# TSOC_USBUART2_R1_1.net
KiCad netlist of a schematic drawn in EAGLE
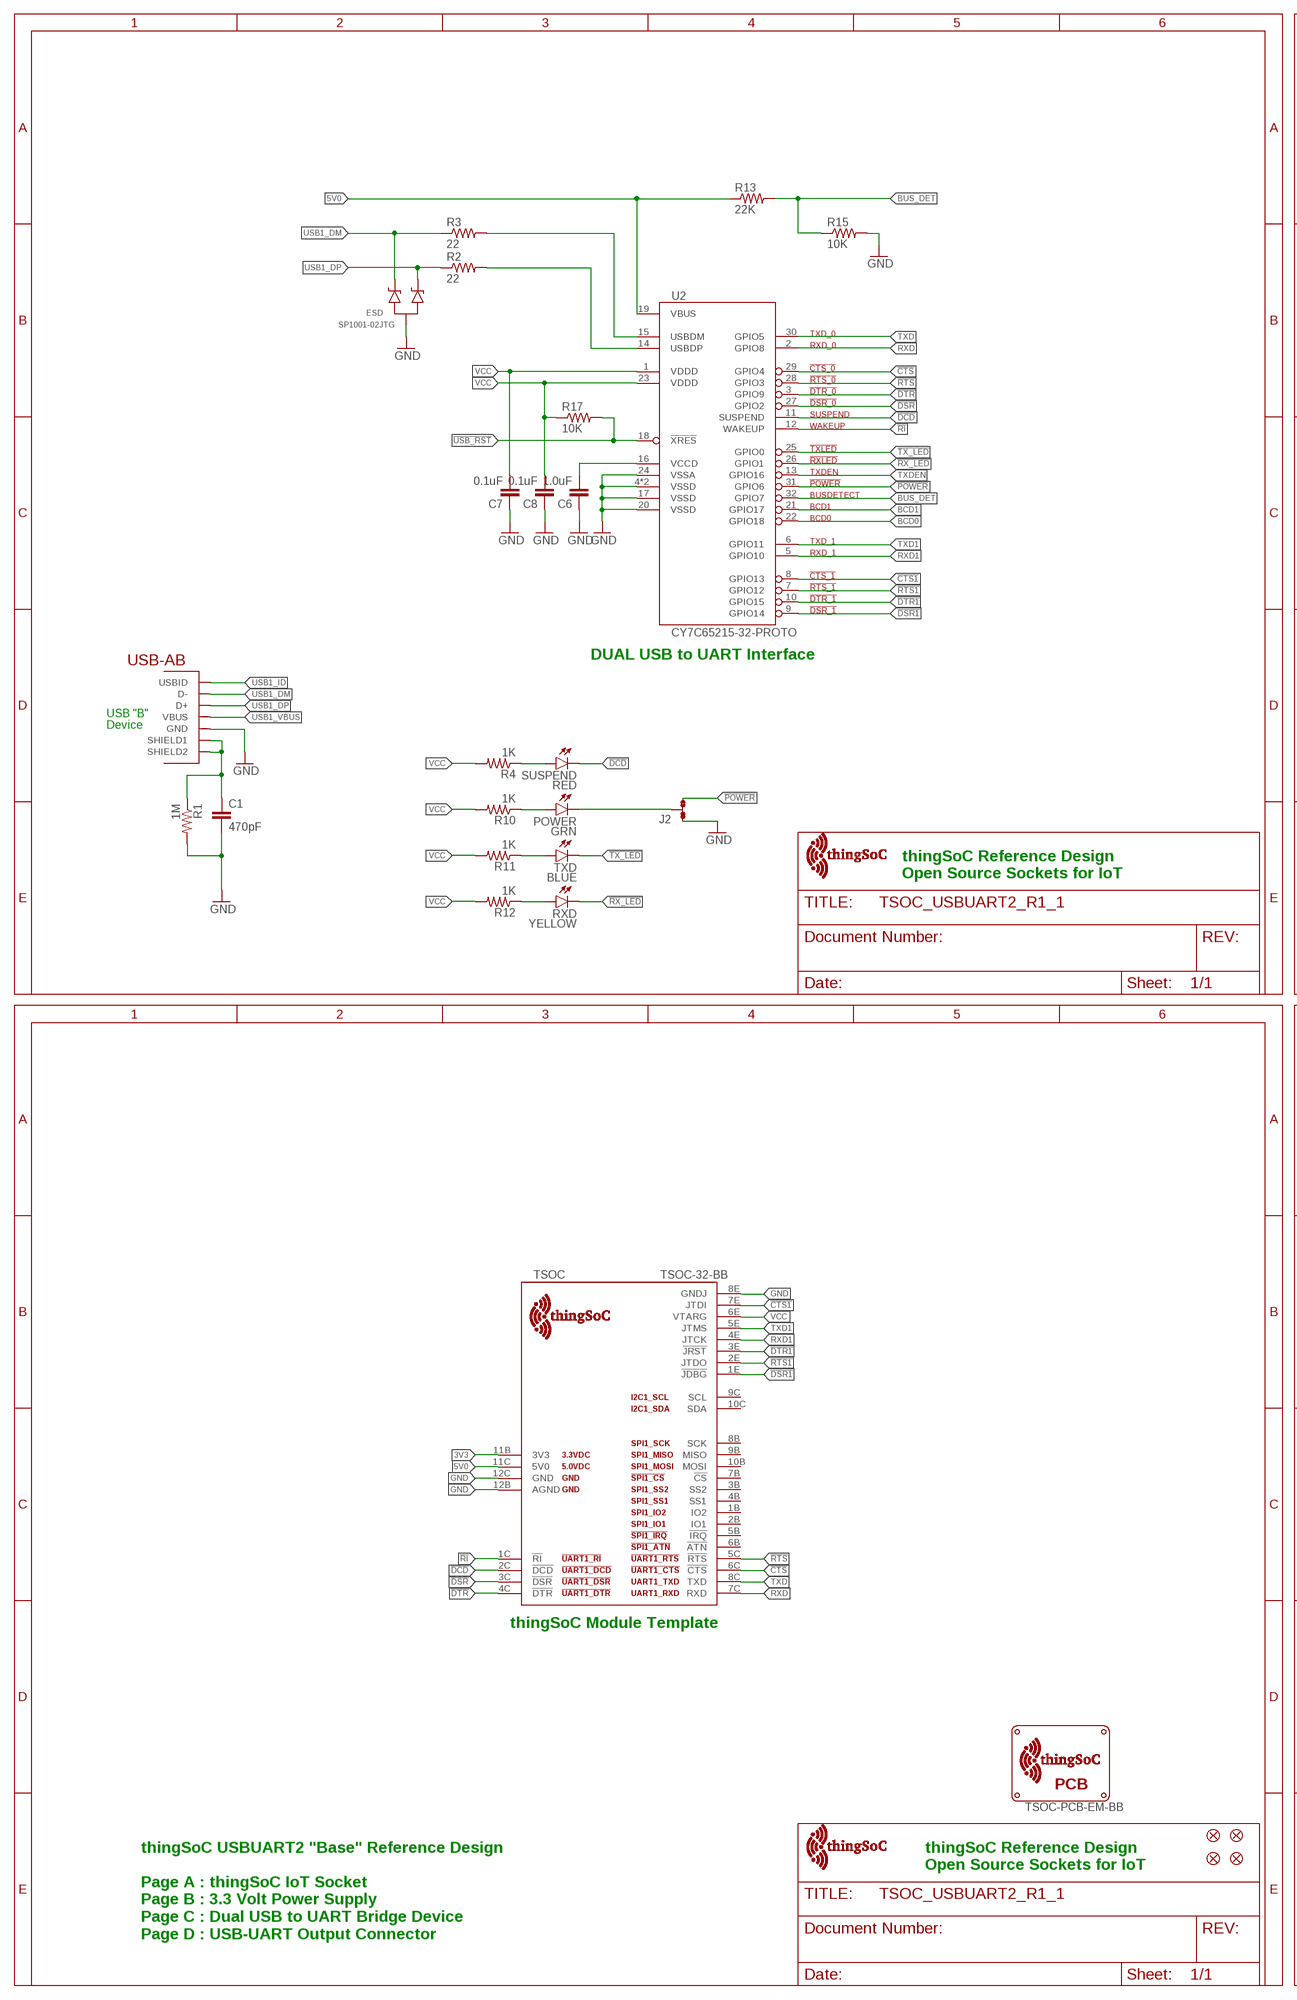
[diagram p0: schematic, sheet 1, part 1 of 2]
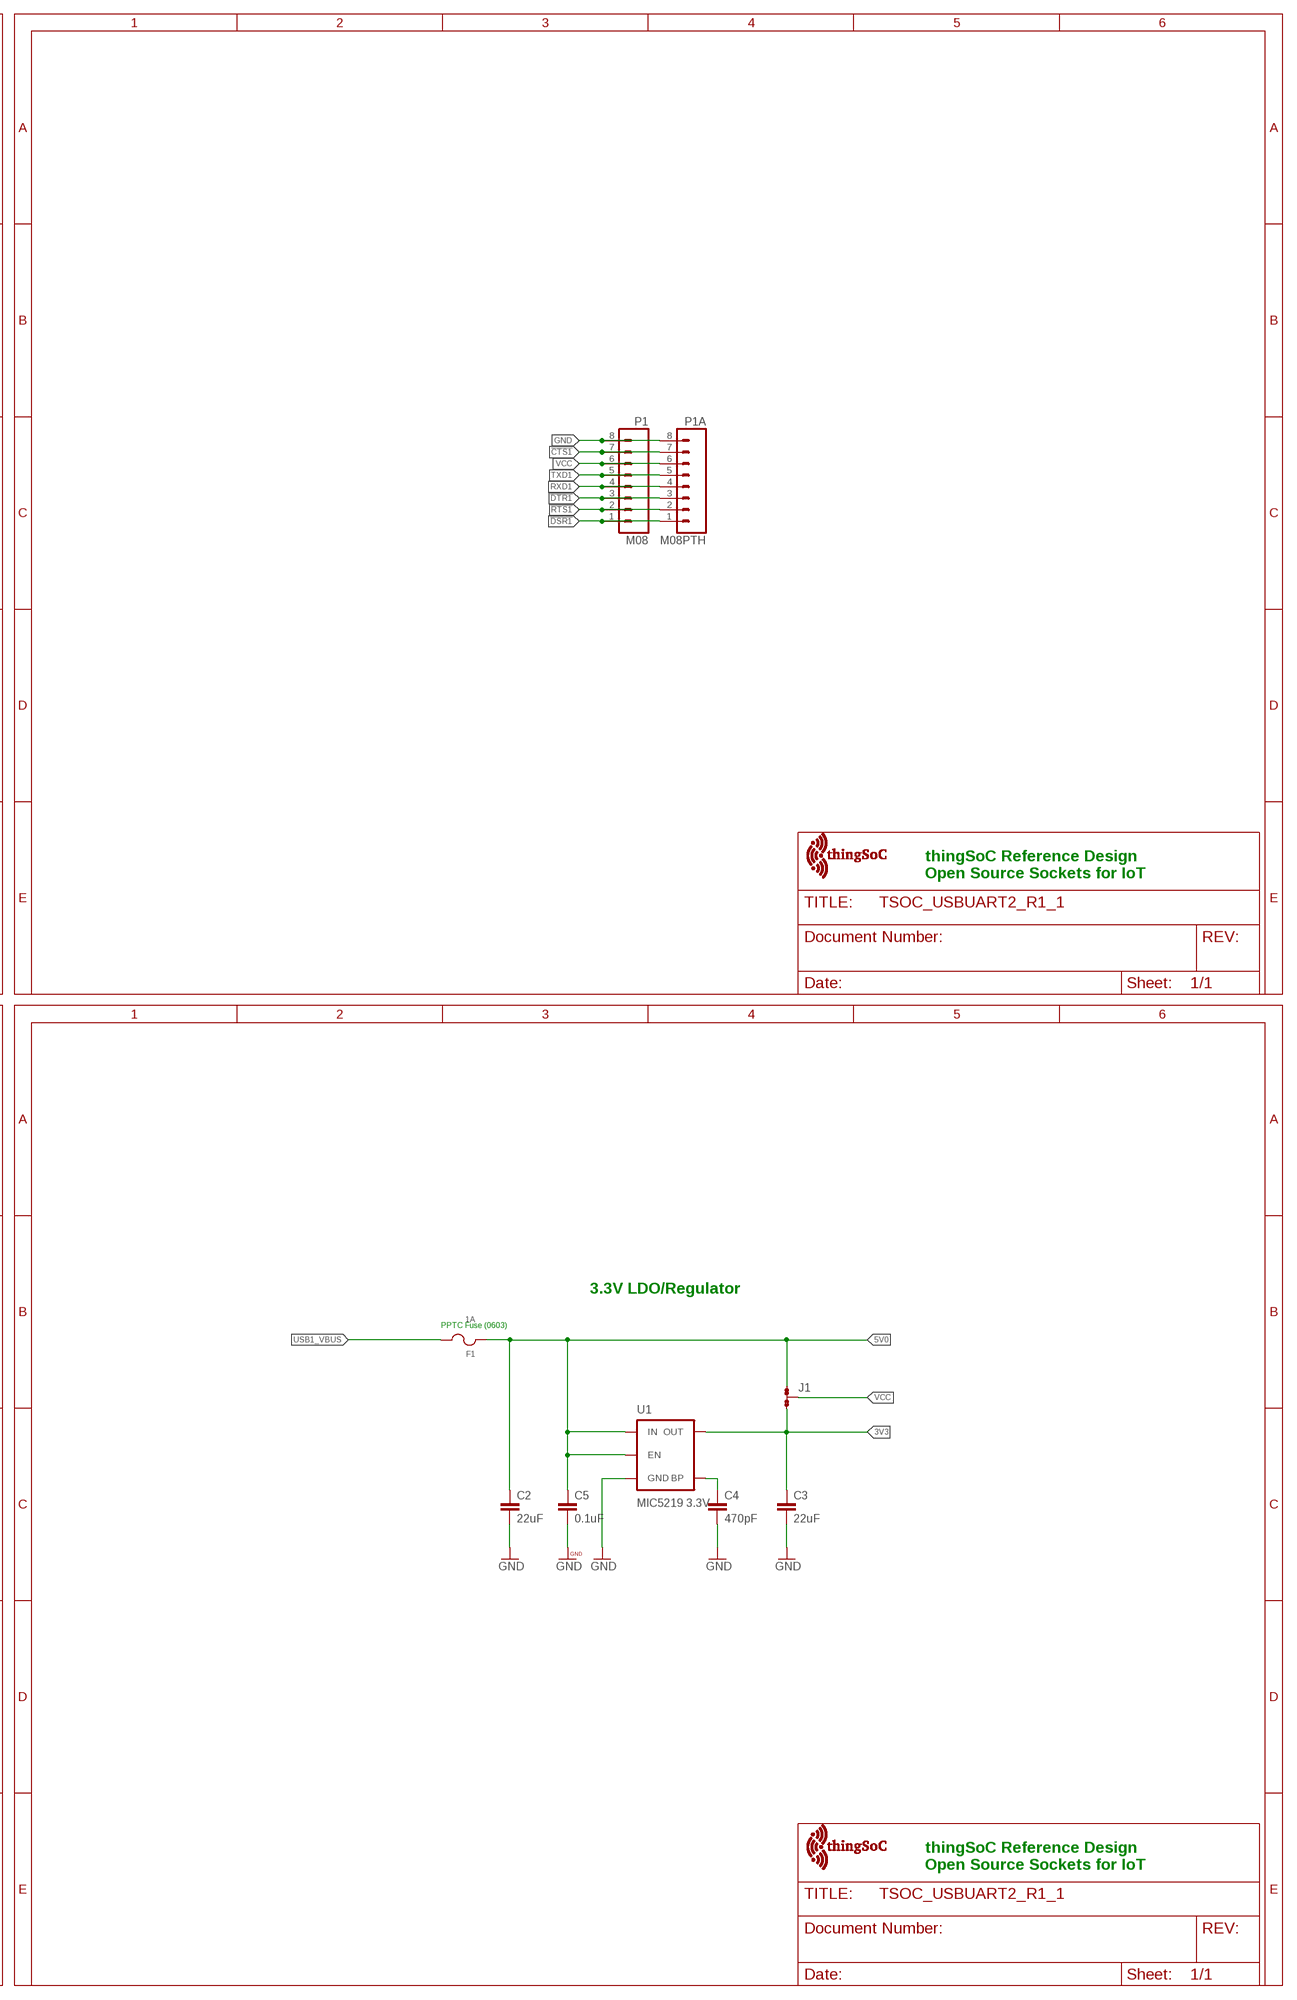
[diagram p1: schematic, sheet 1, part 2 of 2]

(export (version "E")
  (design (tool "Eeschema 10.0.6"))
  (components
    (comp (ref "C1")
      (value "470pF")
      (footprint "eagle-import:EIA-0603")
      (libsource (lib "eagle-import") (part "CAP-0603"))
    )
    (comp (ref "C2")
      (value "22uF")
      (footprint "eagle-import:EIA-1206")
      (libsource (lib "eagle-import") (part "CAP-1206"))
    )
    (comp (ref "C3")
      (value "22uF")
      (footprint "eagle-import:EIA-1206")
      (libsource (lib "eagle-import") (part "CAP-1206"))
    )
    (comp (ref "C4")
      (value "470pF")
      (footprint "eagle-import:EIA-0603")
      (libsource (lib "eagle-import") (part "CAP-0603"))
    )
    (comp (ref "C5")
      (value "0.1uF")
      (footprint "eagle-import:EIA-0603")
      (libsource (lib "eagle-import") (part "CAP-0603"))
    )
    (comp (ref "C6")
      (value "1.0uF")
      (footprint "eagle-import:EIA-0603")
      (libsource (lib "eagle-import") (part "CAP-0603"))
    )
    (comp (ref "C7")
      (value "0.1uF")
      (footprint "eagle-import:EIA-0603")
      (libsource (lib "eagle-import") (part "CAP-0603"))
    )
    (comp (ref "C8")
      (value "0.1uF")
      (footprint "eagle-import:EIA-0603")
      (libsource (lib "eagle-import") (part "CAP-0603"))
    )
    (comp (ref "ESD")
      (value "SP1001-02JTG")
      (footprint "eagle-import:SC70-3")
      (libsource (lib "eagle-import") (part "SP1001-02JTG"))
    )
    (comp (ref "F1")
      (value "1A")
      (footprint "eagle-import:EIA-0603")
      (libsource (lib "eagle-import") (part "FUSE"))
    )
    (comp (ref "FID1")
      (value "FIDUCIALUFIDUCIAL")
      (footprint "eagle-import:MICRO-FIDUCIAL")
      (libsource (lib "eagle-import") (part "FIDUCIALUFIDUCIAL"))
    )
    (comp (ref "FID2")
      (value "FIDUCIALUFIDUCIAL")
      (footprint "eagle-import:MICRO-FIDUCIAL")
      (libsource (lib "eagle-import") (part "FIDUCIALUFIDUCIAL"))
    )
    (comp (ref "FID3")
      (value "FIDUCIALUFIDUCIAL")
      (footprint "eagle-import:MICRO-FIDUCIAL")
      (libsource (lib "eagle-import") (part "FIDUCIALUFIDUCIAL"))
    )
    (comp (ref "FID4")
      (value "FIDUCIALUFIDUCIAL")
      (footprint "eagle-import:MICRO-FIDUCIAL")
      (libsource (lib "eagle-import") (part "FIDUCIALUFIDUCIAL"))
    )
    (comp (ref "J1")
      (value "JMP-3-1_2")
      (footprint "eagle-import:JMP-3-1_2")
      (libsource (lib "eagle-import") (part "JMP-3-1_2"))
    )
    (comp (ref "J2")
      (value "JMP-3-1_2")
      (footprint "eagle-import:JMP-3-1_2")
      (libsource (lib "eagle-import") (part "JMP-3-1_2"))
    )
    (comp (ref "P1")
      (value "M08")
      (footprint "eagle-import:1X08-SMD-FEMALE")
      (libsource (lib "eagle-import") (part "M08"))
    )
    (comp (ref "P1A")
      (value "M08PTH")
      (footprint "eagle-import:1X08")
      (libsource (lib "eagle-import") (part "M08PTH"))
    )
    (comp (ref "POWER")
      (value "GRN")
      (footprint "eagle-import:LED-0603")
      (libsource (lib "eagle-import") (part "LED0603"))
    )
    (comp (ref "R1")
      (value "1M")
      (footprint "eagle-import:EIA-0603")
      (libsource (lib "eagle-import") (part "RESISTOR-0603"))
    )
    (comp (ref "R2")
      (value "22")
      (footprint "eagle-import:EIA-0603")
      (libsource (lib "eagle-import") (part "RESISTOR-0603"))
    )
    (comp (ref "R3")
      (value "22")
      (footprint "eagle-import:EIA-0603")
      (libsource (lib "eagle-import") (part "RESISTOR-0603"))
    )
    (comp (ref "R4")
      (value "1K")
      (footprint "eagle-import:EIA-0603")
      (libsource (lib "eagle-import") (part "RESISTOR-0603"))
    )
    (comp (ref "R10")
      (value "1K")
      (footprint "eagle-import:EIA-0603")
      (libsource (lib "eagle-import") (part "RESISTOR-0603"))
    )
    (comp (ref "R11")
      (value "1K")
      (footprint "eagle-import:EIA-0603")
      (libsource (lib "eagle-import") (part "RESISTOR-0603"))
    )
    (comp (ref "R12")
      (value "1K")
      (footprint "eagle-import:EIA-0603")
      (libsource (lib "eagle-import") (part "RESISTOR-0603"))
    )
    (comp (ref "R13")
      (value "22K")
      (footprint "eagle-import:EIA-0603")
      (libsource (lib "eagle-import") (part "RESISTOR-0603"))
    )
    (comp (ref "R15")
      (value "10K")
      (footprint "eagle-import:EIA-0603")
      (libsource (lib "eagle-import") (part "RESISTOR-0603"))
    )
    (comp (ref "R17")
      (value "10K")
      (footprint "eagle-import:EIA-0603")
      (libsource (lib "eagle-import") (part "RESISTOR-0603"))
    )
    (comp (ref "RXD")
      (value "YELLOW")
      (footprint "eagle-import:LED-0603")
      (libsource (lib "eagle-import") (part "LED0603"))
    )
    (comp (ref "SUSPEND")
      (value "RED")
      (footprint "eagle-import:LED-0603")
      (libsource (lib "eagle-import") (part "LED0603"))
    )
    (comp (ref "TSOC")
      (value "TSOC-32-BB")
      (footprint "eagle-import:TSOC-BB-S32")
      (libsource (lib "eagle-import") (part "TSOC-32-BB"))
    )
    (comp (ref "TXD")
      (value "BLUE")
      (footprint "eagle-import:LED-0603")
      (libsource (lib "eagle-import") (part "LED0603"))
    )
    (comp (ref "U$1")
      (value "TSOC-PCB-EM-BB")
      (footprint "eagle-import:TSOC-EM-BB")
      (libsource (lib "eagle-import") (part "TSOC-PCB-EM-BB"))
    )
    (comp (ref "U$3")
      (value "TSOC-LOGO-LRG")
      (footprint "eagle-import:TSOC-LOGO-LRG")
      (libsource (lib "eagle-import") (part "TSOC-LOGO-LRG"))
    )
    (comp (ref "U$4")
      (value "TSOC-LOGO")
      (footprint "eagle-import:TSOC-LOGO-BLANK")
      (libsource (lib "eagle-import") (part "TSOC-LOGO"))
    )
    (comp (ref "U$5")
      (value "TSOC-LOGO")
      (footprint "eagle-import:TSOC-LOGO-BLANK")
      (libsource (lib "eagle-import") (part "TSOC-LOGO"))
    )
    (comp (ref "U$6")
      (value "TSOC-LOGO")
      (footprint "eagle-import:TSOC-LOGO-BLANK")
      (libsource (lib "eagle-import") (part "TSOC-LOGO"))
    )
    (comp (ref "U1")
      (value "MIC5219 3.3V")
      (footprint "eagle-import:SOT23-5")
      (libsource (lib "eagle-import") (part "V_REG_MIC52193.3V"))
    )
    (comp (ref "U2")
      (value "CY7C65215-32-PROTO")
      (footprint "eagle-import:QFN32-PROTO")
      (libsource (lib "eagle-import") (part "CY7C65215-32-PROTO"))
    )
    (comp (ref "USB")
      (value "USB_AB")
      (footprint "eagle-import:USB-AB-MICRO-SMD")
      (libsource (lib "eagle-import") (part "USB_AB"))
    )
  )
  (nets
    (net (code "1") (name "/~{CTS1}") (class "Default")
      (node (ref "P1") (pin "7") (pinfunction "7_7") (pintype "passive"))
      (node (ref "P1A") (pin "7") (pinfunction "7_7") (pintype "passive"))
      (node (ref "TSOC") (pin "7E") (pinfunction "JTDI_7E") (pintype "bidirectional"))
      (node (ref "U2") (pin "8") (pinfunction "GPIO13_8") (pintype "input"))
    )
    (net (code "2") (name "/~{CTS}") (class "Default")
      (node (ref "TSOC") (pin "6C") (pinfunction "~{CTS}_6C") (pintype "bidirectional"))
      (node (ref "U2") (pin "29") (pinfunction "GPIO4_29") (pintype "input"))
    )
    (net (code "3") (name "/~{DCD}") (class "Default")
      (node (ref "SUSPEND") (pin "C") (pinfunction "C_C") (pintype "passive"))
      (node (ref "TSOC") (pin "2C") (pinfunction "~{DCD}_2C") (pintype "bidirectional"))
      (node (ref "U2") (pin "11") (pinfunction "SUSPEND_11") (pintype "input"))
    )
    (net (code "4") (name "/~{DSR1}") (class "Default")
      (node (ref "P1") (pin "1") (pinfunction "1_1") (pintype "passive"))
      (node (ref "P1A") (pin "1") (pinfunction "1_1") (pintype "passive"))
      (node (ref "TSOC") (pin "1E") (pinfunction "~{JDBG}_1E") (pintype "bidirectional"))
      (node (ref "U2") (pin "9") (pinfunction "GPIO14_9") (pintype "input"))
    )
    (net (code "5") (name "/~{DSR}") (class "Default")
      (node (ref "TSOC") (pin "3C") (pinfunction "~{DSR}_3C") (pintype "bidirectional"))
      (node (ref "U2") (pin "27") (pinfunction "GPIO2_27") (pintype "input"))
    )
    (net (code "6") (name "/~{DTR1}") (class "Default")
      (node (ref "P1") (pin "3") (pinfunction "3_3") (pintype "passive"))
      (node (ref "P1A") (pin "3") (pinfunction "3_3") (pintype "passive"))
      (node (ref "TSOC") (pin "3E") (pinfunction "~{JRST}_3E") (pintype "bidirectional"))
      (node (ref "U2") (pin "10") (pinfunction "GPIO15_10") (pintype "output"))
    )
    (net (code "7") (name "/~{DTR}") (class "Default")
      (node (ref "TSOC") (pin "4C") (pinfunction "~{DTR}_4C") (pintype "bidirectional"))
      (node (ref "U2") (pin "3") (pinfunction "GPIO9_3") (pintype "output"))
    )
    (net (code "8") (name "/~{POWER}") (class "Default")
      (node (ref "J2") (pin "3") (pinfunction "3_3") (pintype "passive"))
      (node (ref "U2") (pin "31") (pinfunction "GPIO6_31") (pintype "input"))
    )
    (net (code "9") (name "/~{RI}") (class "Default")
      (node (ref "TSOC") (pin "1C") (pinfunction "~{RI}_1C") (pintype "bidirectional"))
      (node (ref "U2") (pin "12") (pinfunction "WAKEUP_12") (pintype "input"))
    )
    (net (code "10") (name "/~{RTS1}") (class "Default")
      (node (ref "P1") (pin "2") (pinfunction "2_2") (pintype "passive"))
      (node (ref "P1A") (pin "2") (pinfunction "2_2") (pintype "passive"))
      (node (ref "TSOC") (pin "2E") (pinfunction "JTDO_2E") (pintype "bidirectional"))
      (node (ref "U2") (pin "7") (pinfunction "GPIO12_7") (pintype "output"))
    )
    (net (code "11") (name "/~{RTS}") (class "Default")
      (node (ref "TSOC") (pin "5C") (pinfunction "~{RTS}_5C") (pintype "bidirectional"))
      (node (ref "U2") (pin "28") (pinfunction "GPIO3_28") (pintype "output"))
    )
    (net (code "12") (name "/~{RX_LED}") (class "Default")
      (node (ref "RXD") (pin "C") (pinfunction "C_C") (pintype "passive"))
      (node (ref "U2") (pin "26") (pinfunction "GPIO1_26") (pintype "input"))
    )
    (net (code "13") (name "/~{TX_LED}") (class "Default")
      (node (ref "TXD") (pin "C") (pinfunction "C_C") (pintype "passive"))
      (node (ref "U2") (pin "25") (pinfunction "GPIO0_25") (pintype "input"))
    )
    (net (code "14") (name "/~{USB_RST}") (class "Default")
      (node (ref "R17") (pin "2") (pinfunction "2_2") (pintype "passive"))
      (node (ref "U2") (pin "18") (pinfunction "~{XRES}_18") (pintype "input"))
    )
    (net (code "15") (name "3V3") (class "Default")
      (node (ref "C3") (pin "1") (pinfunction "1_1") (pintype "passive"))
      (node (ref "J1") (pin "3") (pinfunction "3_3") (pintype "passive"))
      (node (ref "TSOC") (pin "11B") (pinfunction "3V3_11B") (pintype "bidirectional"))
      (node (ref "U1") (pin "5") (pinfunction "OUT_5") (pintype "passive"))
    )
    (net (code "16") (name "5V0") (class "Default")
      (node (ref "C2") (pin "1") (pinfunction "1_1") (pintype "passive"))
      (node (ref "C5") (pin "1") (pinfunction "1_1") (pintype "passive"))
      (node (ref "F1") (pin "1") (pinfunction "P$1_1") (pintype "bidirectional"))
      (node (ref "J1") (pin "1") (pinfunction "1_1") (pintype "passive"))
      (node (ref "R13") (pin "1") (pinfunction "1_1") (pintype "passive"))
      (node (ref "TSOC") (pin "11C") (pinfunction "5V0_11C") (pintype "bidirectional"))
      (node (ref "U1") (pin "1") (pinfunction "IN_1") (pintype "input"))
      (node (ref "U1") (pin "3") (pinfunction "EN_3") (pintype "input"))
      (node (ref "U2") (pin "19") (pinfunction "VBUS_19") (pintype "power_in"))
    )
    (net (code "17") (name "BCD0") (class "Default")
      (node (ref "U2") (pin "22") (pinfunction "GPIO18_22") (pintype "input"))
    )
    (net (code "18") (name "BCD1") (class "Default")
      (node (ref "U2") (pin "21") (pinfunction "GPIO17_21") (pintype "input"))
    )
    (net (code "19") (name "BUS_DET") (class "Default")
      (node (ref "R13") (pin "2") (pinfunction "2_2") (pintype "passive"))
      (node (ref "R15") (pin "1") (pinfunction "1_1") (pintype "passive"))
      (node (ref "U2") (pin "32") (pinfunction "GPIO7_32") (pintype "input"))
    )
    (net (code "20") (name "GND") (class "Default")
      (node (ref "C1") (pin "2") (pinfunction "2_2") (pintype "passive"))
      (node (ref "C2") (pin "2") (pinfunction "2_2") (pintype "passive"))
      (node (ref "C3") (pin "2") (pinfunction "2_2") (pintype "passive"))
      (node (ref "C4") (pin "2") (pinfunction "2_2") (pintype "passive"))
      (node (ref "C5") (pin "2") (pinfunction "2_2") (pintype "passive"))
      (node (ref "C6") (pin "1") (pinfunction "1_1") (pintype "passive"))
      (node (ref "C7") (pin "1") (pinfunction "1_1") (pintype "passive"))
      (node (ref "C8") (pin "1") (pinfunction "1_1") (pintype "passive"))
      (node (ref "ESD") (pin "3") (pinfunction "A_3") (pintype "passive"))
      (node (ref "J2") (pin "1") (pinfunction "1_1") (pintype "passive"))
      (node (ref "P1") (pin "8") (pinfunction "8_8") (pintype "passive"))
      (node (ref "P1A") (pin "8") (pinfunction "8_8") (pintype "passive"))
      (node (ref "R1") (pin "2") (pinfunction "2_2") (pintype "passive"))
      (node (ref "R15") (pin "2") (pinfunction "2_2") (pintype "passive"))
      (node (ref "TSOC") (pin "12B") (pinfunction "AGND_12B") (pintype "bidirectional"))
      (node (ref "TSOC") (pin "12C") (pinfunction "GND_12C") (pintype "bidirectional"))
      (node (ref "TSOC") (pin "8E") (pinfunction "GNDJ_8E") (pintype "bidirectional"))
      (node (ref "U1") (pin "2") (pinfunction "GND_2") (pintype "input"))
      (node (ref "U2") (pin "17") (pinfunction "VSSD_17") (pintype "power_in"))
      (node (ref "U2") (pin "20") (pinfunction "VSSD_20") (pintype "power_in"))
      (node (ref "U2") (pin "24") (pinfunction "VSSA_24") (pintype "power_in"))
      (node (ref "U2") (pin "4") (pinfunction "VSSD_4") (pintype "power_in"))
      (node (ref "U2") (pin "EXP") (pinfunction "VSSD_EXP") (pintype "power_in"))
      (node (ref "USB") (pin "GND") (pinfunction "GND_GND") (pintype "bidirectional"))
    )
    (net (code "21") (name "Net-(C1-Pad1)") (class "Default")
      (node (ref "C1") (pin "1") (pinfunction "1_1") (pintype "passive"))
      (node (ref "R1") (pin "1") (pinfunction "1_1") (pintype "passive"))
      (node (ref "USB") (pin "SHIELD1") (pinfunction "SHIELD1_SHIELD1") (pintype "bidirectional"))
      (node (ref "USB") (pin "SHIELD2") (pinfunction "SHIELD2_SHIELD2") (pintype "bidirectional"))
    )
    (net (code "22") (name "Net-(J2-Pad2)") (class "Default")
      (node (ref "J2") (pin "2") (pinfunction "2_2") (pintype "passive"))
      (node (ref "POWER") (pin "C") (pinfunction "C_C") (pintype "passive"))
    )
    (net (code "23") (name "Net-(POWER-PadA)") (class "Default")
      (node (ref "POWER") (pin "A") (pinfunction "A_A") (pintype "passive"))
      (node (ref "R10") (pin "1") (pinfunction "1_1") (pintype "passive"))
    )
    (net (code "24") (name "Net-(R4-Pad1)") (class "Default")
      (node (ref "R4") (pin "1") (pinfunction "1_1") (pintype "passive"))
      (node (ref "SUSPEND") (pin "A") (pinfunction "A_A") (pintype "passive"))
    )
    (net (code "25") (name "Net-(R11-Pad1)") (class "Default")
      (node (ref "R11") (pin "1") (pinfunction "1_1") (pintype "passive"))
      (node (ref "TXD") (pin "A") (pinfunction "A_A") (pintype "passive"))
    )
    (net (code "26") (name "Net-(R12-Pad1)") (class "Default")
      (node (ref "R12") (pin "1") (pinfunction "1_1") (pintype "passive"))
      (node (ref "RXD") (pin "A") (pinfunction "A_A") (pintype "passive"))
    )
    (net (code "27") (name "Net-(U1-BP)") (class "Default")
      (node (ref "C4") (pin "1") (pinfunction "1_1") (pintype "passive"))
      (node (ref "U1") (pin "4") (pinfunction "BP_4") (pintype "input"))
    )
    (net (code "28") (name "Net-(U2-USBDM)") (class "Default")
      (node (ref "R3") (pin "2") (pinfunction "2_2") (pintype "passive"))
      (node (ref "U2") (pin "15") (pinfunction "USBDM_15") (pintype "bidirectional"))
    )
    (net (code "29") (name "Net-(U2-USBDP)") (class "Default")
      (node (ref "R2") (pin "2") (pinfunction "2_2") (pintype "passive"))
      (node (ref "U2") (pin "14") (pinfunction "USBDP_14") (pintype "bidirectional"))
    )
    (net (code "30") (name "Net-(U2-VCCD)") (class "Default")
      (node (ref "C6") (pin "2") (pinfunction "2_2") (pintype "passive"))
      (node (ref "U2") (pin "16") (pinfunction "VCCD_16") (pintype "output"))
    )
    (net (code "31") (name "RXD") (class "Default")
      (node (ref "TSOC") (pin "7C") (pinfunction "RXD_7C") (pintype "bidirectional"))
      (node (ref "U2") (pin "2") (pinfunction "GPIO8_2") (pintype "input"))
    )
    (net (code "32") (name "RXD1") (class "Default")
      (node (ref "P1") (pin "4") (pinfunction "4_4") (pintype "passive"))
      (node (ref "P1A") (pin "4") (pinfunction "4_4") (pintype "passive"))
      (node (ref "TSOC") (pin "4E") (pinfunction "JTCK_4E") (pintype "bidirectional"))
      (node (ref "U2") (pin "5") (pinfunction "GPIO10_5") (pintype "input"))
    )
    (net (code "33") (name "TXD") (class "Default")
      (node (ref "TSOC") (pin "8C") (pinfunction "TXD_8C") (pintype "bidirectional"))
      (node (ref "U2") (pin "30") (pinfunction "GPIO5_30") (pintype "output"))
    )
    (net (code "34") (name "TXD1") (class "Default")
      (node (ref "P1") (pin "5") (pinfunction "5_5") (pintype "passive"))
      (node (ref "P1A") (pin "5") (pinfunction "5_5") (pintype "passive"))
      (node (ref "TSOC") (pin "5E") (pinfunction "JTMS_5E") (pintype "bidirectional"))
      (node (ref "U2") (pin "6") (pinfunction "GPIO11_6") (pintype "output"))
    )
    (net (code "35") (name "TXDEN") (class "Default")
      (node (ref "U2") (pin "13") (pinfunction "GPIO16_13") (pintype "output"))
    )
    (net (code "36") (name "USB1_DM") (class "Default")
      (node (ref "ESD") (pin "2") (pinfunction "C2_2") (pintype "passive"))
      (node (ref "R3") (pin "1") (pinfunction "1_1") (pintype "passive"))
      (node (ref "USB") (pin "D-") (pinfunction "D-_D-") (pintype "bidirectional"))
    )
    (net (code "37") (name "USB1_DP") (class "Default")
      (node (ref "ESD") (pin "1") (pinfunction "C1_1") (pintype "passive"))
      (node (ref "R2") (pin "1") (pinfunction "1_1") (pintype "passive"))
      (node (ref "USB") (pin "D+") (pinfunction "D+_D+") (pintype "bidirectional"))
    )
    (net (code "38") (name "USB1_ID") (class "Default")
      (node (ref "USB") (pin "ID") (pinfunction "USBID_ID") (pintype "bidirectional"))
    )
    (net (code "39") (name "USB1_VBUS") (class "Default")
      (node (ref "F1") (pin "2") (pinfunction "P$2_2") (pintype "bidirectional"))
      (node (ref "USB") (pin "VBUS") (pinfunction "VBUS_VBUS") (pintype "bidirectional"))
    )
    (net (code "40") (name "VCC") (class "Default")
      (node (ref "C7") (pin "2") (pinfunction "2_2") (pintype "passive"))
      (node (ref "C8") (pin "2") (pinfunction "2_2") (pintype "passive"))
      (node (ref "J1") (pin "2") (pinfunction "2_2") (pintype "passive"))
      (node (ref "P1") (pin "6") (pinfunction "6_6") (pintype "passive"))
      (node (ref "P1A") (pin "6") (pinfunction "6_6") (pintype "passive"))
      (node (ref "R10") (pin "2") (pinfunction "2_2") (pintype "passive"))
      (node (ref "R11") (pin "2") (pinfunction "2_2") (pintype "passive"))
      (node (ref "R12") (pin "2") (pinfunction "2_2") (pintype "passive"))
      (node (ref "R17") (pin "1") (pinfunction "1_1") (pintype "passive"))
      (node (ref "R4") (pin "2") (pinfunction "2_2") (pintype "passive"))
      (node (ref "TSOC") (pin "6E") (pinfunction "VTARG_6E") (pintype "bidirectional"))
      (node (ref "U2") (pin "1") (pinfunction "VDDD_1") (pintype "power_in"))
      (node (ref "U2") (pin "23") (pinfunction "VDDD_23") (pintype "power_in"))
    )
    (net (code "41") (name "unconnected-(TSOC-IO1-Pad2B)") (class "Default")
      (node (ref "TSOC") (pin "2B") (pinfunction "IO1_2B") (pintype "bidirectional"))
    )
    (net (code "42") (name "unconnected-(TSOC-IO2-Pad1B)") (class "Default")
      (node (ref "TSOC") (pin "1B") (pinfunction "IO2_1B") (pintype "bidirectional"))
    )
    (net (code "43") (name "unconnected-(TSOC-MISO-Pad9B)") (class "Default")
      (node (ref "TSOC") (pin "9B") (pinfunction "MISO_9B") (pintype "bidirectional"))
    )
    (net (code "44") (name "unconnected-(TSOC-MOSI-Pad10B)") (class "Default")
      (node (ref "TSOC") (pin "10B") (pinfunction "MOSI_10B") (pintype "bidirectional"))
    )
    (net (code "45") (name "unconnected-(TSOC-SCK-Pad8B)") (class "Default")
      (node (ref "TSOC") (pin "8B") (pinfunction "SCK_8B") (pintype "bidirectional"))
    )
    (net (code "46") (name "unconnected-(TSOC-SCL-Pad9C)") (class "Default")
      (node (ref "TSOC") (pin "9C") (pinfunction "SCL_9C") (pintype "bidirectional"))
    )
    (net (code "47") (name "unconnected-(TSOC-SDA-Pad10C)") (class "Default")
      (node (ref "TSOC") (pin "10C") (pinfunction "SDA_10C") (pintype "bidirectional"))
    )
    (net (code "48") (name "unconnected-(TSOC-SS1-Pad4B)") (class "Default")
      (node (ref "TSOC") (pin "4B") (pinfunction "SS1_4B") (pintype "bidirectional"))
    )
    (net (code "49") (name "unconnected-(TSOC-SS2-Pad3B)") (class "Default")
      (node (ref "TSOC") (pin "3B") (pinfunction "SS2_3B") (pintype "bidirectional"))
    )
    (net (code "50") (name "unconnected-(TSOC-~{ATN}-Pad6B)") (class "Default")
      (node (ref "TSOC") (pin "6B") (pinfunction "~{ATN}_6B") (pintype "bidirectional"))
    )
    (net (code "51") (name "unconnected-(TSOC-~{CS}-Pad7B)") (class "Default")
      (node (ref "TSOC") (pin "7B") (pinfunction "~{CS}_7B") (pintype "bidirectional"))
    )
    (net (code "52") (name "unconnected-(TSOC-~{IRQ}-Pad5B)") (class "Default")
      (node (ref "TSOC") (pin "5B") (pinfunction "~{IRQ}_5B") (pintype "bidirectional"))
    )
  )
)
